# M220print.net
KiCad netlist of a schematic drawn in EAGLE
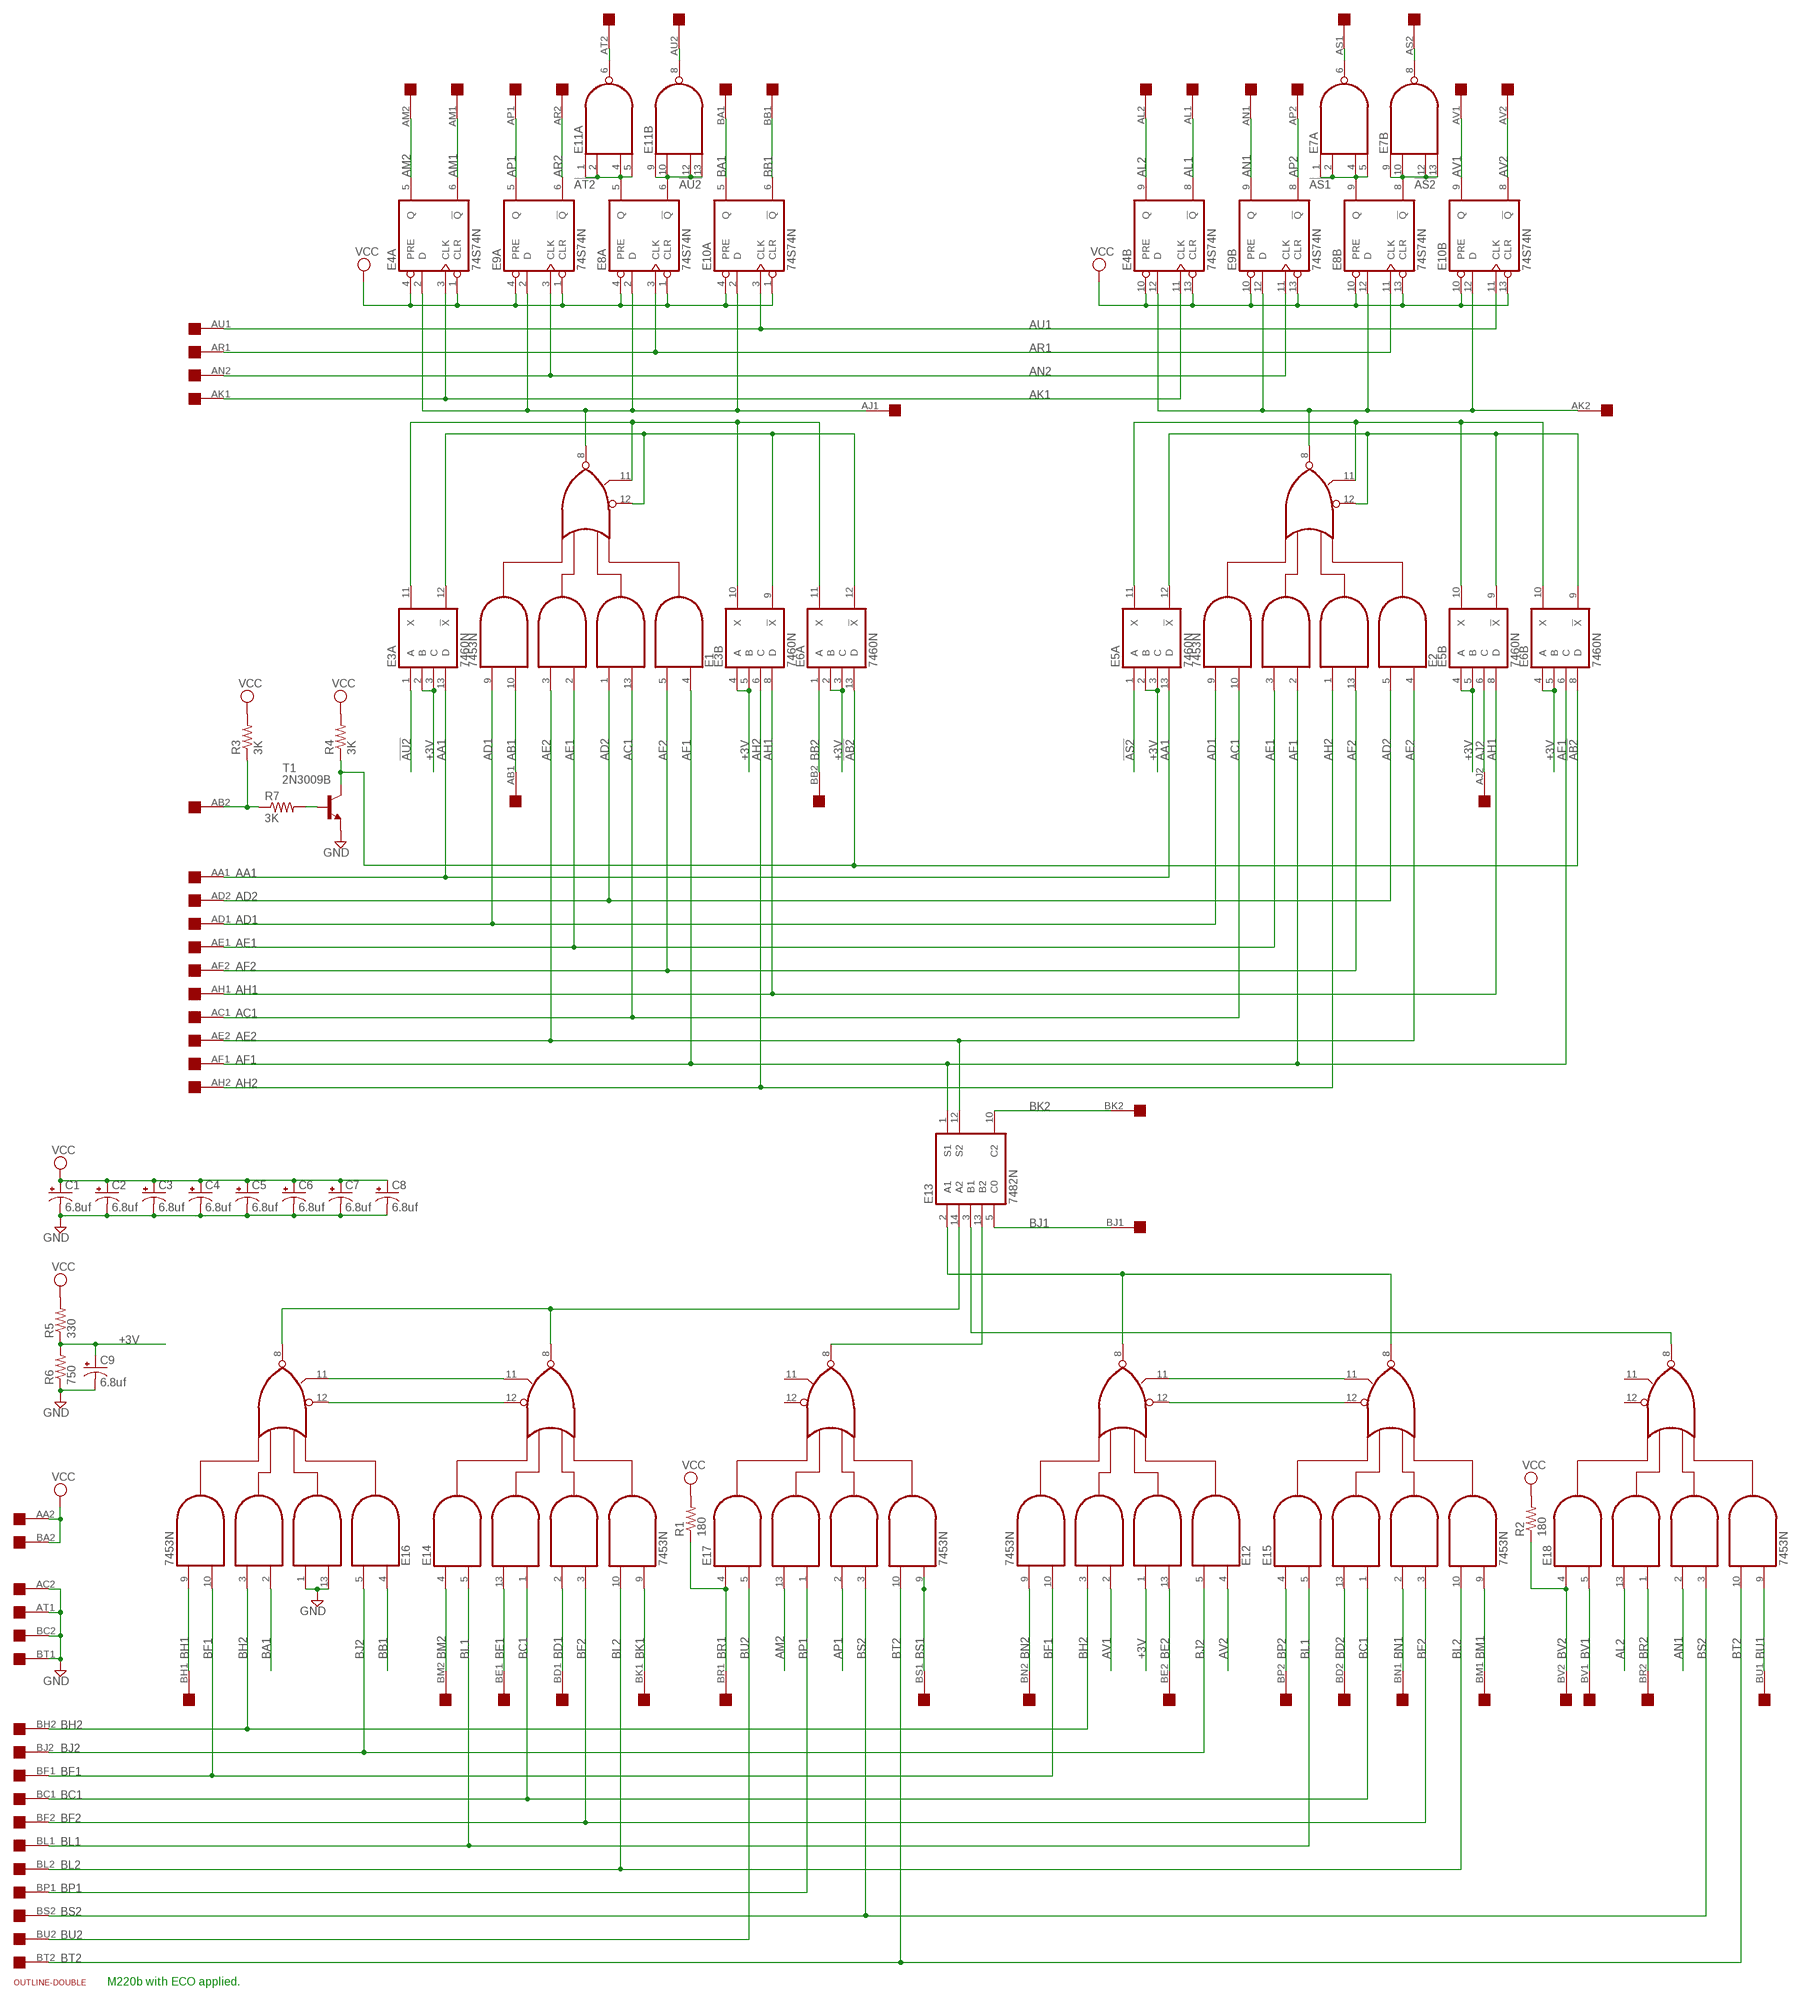
[diagram p0: schematic, sheet 1]

(export (version "E")
  (design (tool "Eeschema 10.0.6"))
  (components
    (comp (ref "C1")
      (value "6.8uf")
      (footprint "eagle-import:E15-5")
      (libsource (lib "eagle-import") (part "CPOL-USE15-5AXIAL"))
    )
    (comp (ref "C2")
      (value "6.8uf")
      (footprint "eagle-import:E15-5")
      (libsource (lib "eagle-import") (part "CPOL-USE15-5AXIAL"))
    )
    (comp (ref "C3")
      (value "6.8uf")
      (footprint "eagle-import:E15-5")
      (libsource (lib "eagle-import") (part "CPOL-USE15-5AXIAL"))
    )
    (comp (ref "C4")
      (value "6.8uf")
      (footprint "eagle-import:E15-5")
      (libsource (lib "eagle-import") (part "CPOL-USE15-5AXIAL"))
    )
    (comp (ref "C5")
      (value "6.8uf")
      (footprint "eagle-import:E15-5")
      (libsource (lib "eagle-import") (part "CPOL-USE15-5AXIAL"))
    )
    (comp (ref "C6")
      (value "6.8uf")
      (footprint "eagle-import:E15-5")
      (libsource (lib "eagle-import") (part "CPOL-USE15-5AXIAL"))
    )
    (comp (ref "C7")
      (value "6.8uf")
      (footprint "eagle-import:E15-5")
      (libsource (lib "eagle-import") (part "CPOL-USE15-5AXIAL"))
    )
    (comp (ref "C8")
      (value "6.8uf")
      (footprint "eagle-import:E15-5")
      (libsource (lib "eagle-import") (part "CPOL-USE15-5AXIAL"))
    )
    (comp (ref "C9")
      (value "6.8uf")
      (footprint "eagle-import:E15-5")
      (libsource (lib "eagle-import") (part "CPOL-USE15-5AXIAL"))
    )
    (comp (ref "E1")
      (value "7453N")
      (footprint "eagle-import:DIL14")
      (libsource (lib "eagle-import") (part "7453N"))
    )
    (comp (ref "E2")
      (value "7453N")
      (footprint "eagle-import:DIL14")
      (libsource (lib "eagle-import") (part "7453N"))
    )
    (comp (ref "E3")
      (value "7460N")
      (footprint "eagle-import:DIL14")
      (libsource (lib "eagle-import") (part "7460N"))
    )
    (comp (ref "E4")
      (value "74S74N")
      (footprint "eagle-import:DIL14")
      (libsource (lib "eagle-import") (part "7474NS"))
    )
    (comp (ref "E5")
      (value "7460N")
      (footprint "eagle-import:DIL14")
      (libsource (lib "eagle-import") (part "7460N"))
    )
    (comp (ref "E6")
      (value "7460N")
      (footprint "eagle-import:DIL14")
      (libsource (lib "eagle-import") (part "7460N"))
    )
    (comp (ref "E7")
      (value "74S20N")
      (footprint "eagle-import:DIL14")
      (libsource (lib "eagle-import") (part "7420NS"))
    )
    (comp (ref "E8")
      (value "74S74N")
      (footprint "eagle-import:DIL14")
      (libsource (lib "eagle-import") (part "7474NS"))
    )
    (comp (ref "E9")
      (value "74S74N")
      (footprint "eagle-import:DIL14")
      (libsource (lib "eagle-import") (part "7474NS"))
    )
    (comp (ref "E10")
      (value "74S74N")
      (footprint "eagle-import:DIL14")
      (libsource (lib "eagle-import") (part "7474NS"))
    )
    (comp (ref "E11")
      (value "74S20N")
      (footprint "eagle-import:DIL14")
      (libsource (lib "eagle-import") (part "7420NS"))
    )
    (comp (ref "E12")
      (value "7453N")
      (footprint "eagle-import:DIL14")
      (libsource (lib "eagle-import") (part "7453N"))
    )
    (comp (ref "E13")
      (value "7482N")
      (footprint "eagle-import:DIL14")
      (libsource (lib "eagle-import") (part "7482N"))
    )
    (comp (ref "E14")
      (value "7453N")
      (footprint "eagle-import:DIL14")
      (libsource (lib "eagle-import") (part "7453N"))
    )
    (comp (ref "E15")
      (value "7453N")
      (footprint "eagle-import:DIL14")
      (libsource (lib "eagle-import") (part "7453N"))
    )
    (comp (ref "E16")
      (value "7453N")
      (footprint "eagle-import:DIL14")
      (libsource (lib "eagle-import") (part "7453N"))
    )
    (comp (ref "E17")
      (value "7453N")
      (footprint "eagle-import:DIL14")
      (libsource (lib "eagle-import") (part "7453N"))
    )
    (comp (ref "E18")
      (value "7453N")
      (footprint "eagle-import:DIL14")
      (libsource (lib "eagle-import") (part "7453N"))
    )
    (comp (ref "R1")
      (value "180")
      (footprint "eagle-import:0207_10")
      (libsource (lib "eagle-import") (part "R-US_0207/10"))
    )
    (comp (ref "R2")
      (value "180")
      (footprint "eagle-import:0207_10")
      (libsource (lib "eagle-import") (part "R-US_0207/10"))
    )
    (comp (ref "R3")
      (value "3K")
      (footprint "eagle-import:0207_10")
      (libsource (lib "eagle-import") (part "R-US_0207/10"))
    )
    (comp (ref "R4")
      (value "3K")
      (footprint "eagle-import:0207_10")
      (libsource (lib "eagle-import") (part "R-US_0207/10"))
    )
    (comp (ref "R5")
      (value "330")
      (footprint "eagle-import:0207_10")
      (libsource (lib "eagle-import") (part "R-US_0207/10"))
    )
    (comp (ref "R6")
      (value "750")
      (footprint "eagle-import:0207_10")
      (libsource (lib "eagle-import") (part "R-US_0207/10"))
    )
    (comp (ref "R7")
      (value "3K")
      (footprint "eagle-import:0207_10")
      (libsource (lib "eagle-import") (part "R-US_0207/10"))
    )
    (comp (ref "T1")
      (value "2N3009B")
      (footprint "eagle-import:TO5")
      (libsource (lib "eagle-import") (part "2N1613"))
    )
    (comp (ref "U$1")
      (value "DOUBLE")
      (footprint "eagle-import:EDGE-CON4")
      (libsource (lib "eagle-import") (part "DOUBLE"))
    )
    (comp (ref "U$2")
      (value "OUTLINE-DOUBLE")
      (footprint "eagle-import:DOUBLE")
      (libsource (lib "eagle-import") (part "OUTLINE-DOUBLE"))
    )
  )
  (nets
    (net (code "1") (name "/+3V") (class "Default")
      (node (ref "C9") (pin "+") (pinfunction "+_+") (pintype "passive"))
      (node (ref "E12") (pin "1") (pinfunction "I4_1") (pintype "input"))
      (node (ref "E3") (pin "2") (pinfunction "B_2") (pintype "input"))
      (node (ref "E3") (pin "3") (pinfunction "C_3") (pintype "input"))
      (node (ref "E3") (pin "4") (pinfunction "A_4") (pintype "input"))
      (node (ref "E3") (pin "5") (pinfunction "B_5") (pintype "input"))
      (node (ref "E5") (pin "2") (pinfunction "B_2") (pintype "input"))
      (node (ref "E5") (pin "3") (pinfunction "C_3") (pintype "input"))
      (node (ref "E5") (pin "4") (pinfunction "A_4") (pintype "input"))
      (node (ref "E5") (pin "5") (pinfunction "B_5") (pintype "input"))
      (node (ref "E6") (pin "2") (pinfunction "B_2") (pintype "input"))
      (node (ref "E6") (pin "3") (pinfunction "C_3") (pintype "input"))
      (node (ref "E6") (pin "4") (pinfunction "A_4") (pintype "input"))
      (node (ref "E6") (pin "5") (pinfunction "B_5") (pintype "input"))
      (node (ref "R5") (pin "1") (pinfunction "1_1") (pintype "passive"))
      (node (ref "R6") (pin "2") (pinfunction "2_2") (pintype "passive"))
    )
    (net (code "2") (name "/AA1") (class "Default")
      (node (ref "E3") (pin "13") (pinfunction "D_13") (pintype "input"))
      (node (ref "E5") (pin "13") (pinfunction "D_13") (pintype "input"))
      (node (ref "U$1") (pin "AA1") (pinfunction "1_AA1") (pintype "passive"))
    )
    (net (code "3") (name "/AB1") (class "Default")
      (node (ref "E1") (pin "10") (pinfunction "I7_10") (pintype "input"))
      (node (ref "U$1") (pin "AB1") (pinfunction "1_AB1") (pintype "passive"))
    )
    (net (code "4") (name "/AC1") (class "Default")
      (node (ref "E1") (pin "13") (pinfunction "I3_13") (pintype "input"))
      (node (ref "E2") (pin "10") (pinfunction "I7_10") (pintype "input"))
      (node (ref "U$1") (pin "AC1") (pinfunction "1_AC1") (pintype "passive"))
    )
    (net (code "5") (name "/AD1") (class "Default")
      (node (ref "E1") (pin "9") (pinfunction "I8_9") (pintype "input"))
      (node (ref "E2") (pin "9") (pinfunction "I8_9") (pintype "input"))
      (node (ref "U$1") (pin "AD1") (pinfunction "1_AD1") (pintype "passive"))
    )
    (net (code "6") (name "/AD2") (class "Default")
      (node (ref "E1") (pin "1") (pinfunction "I4_1") (pintype "input"))
      (node (ref "E2") (pin "5") (pinfunction "I2_5") (pintype "input"))
      (node (ref "U$1") (pin "AD2") (pinfunction "1_AD2") (pintype "passive"))
    )
    (net (code "7") (name "/AE1") (class "Default")
      (node (ref "E1") (pin "2") (pinfunction "I5_2") (pintype "input"))
      (node (ref "E2") (pin "3") (pinfunction "I6_3") (pintype "input"))
      (node (ref "U$1") (pin "AE1") (pinfunction "1_AE1") (pintype "passive"))
    )
    (net (code "8") (name "/AE2") (class "Default")
      (node (ref "E1") (pin "3") (pinfunction "I6_3") (pintype "input"))
      (node (ref "E13") (pin "12") (pinfunction "S2_12") (pintype "output"))
      (node (ref "E2") (pin "4") (pinfunction "I1_4") (pintype "input"))
      (node (ref "U$1") (pin "AE2") (pinfunction "1_AE2") (pintype "passive"))
    )
    (net (code "9") (name "/AF1") (class "Default")
      (node (ref "E1") (pin "4") (pinfunction "I1_4") (pintype "input"))
      (node (ref "E13") (pin "1") (pinfunction "S1_1") (pintype "output"))
      (node (ref "E2") (pin "2") (pinfunction "I5_2") (pintype "input"))
      (node (ref "E6") (pin "6") (pinfunction "C_6") (pintype "input"))
      (node (ref "U$1") (pin "AF1") (pinfunction "1_AF1") (pintype "passive"))
    )
    (net (code "10") (name "/AF2") (class "Default")
      (node (ref "E1") (pin "5") (pinfunction "I2_5") (pintype "input"))
      (node (ref "E2") (pin "13") (pinfunction "I3_13") (pintype "input"))
      (node (ref "U$1") (pin "AF2") (pinfunction "1_AF2") (pintype "passive"))
    )
    (net (code "11") (name "/AH1") (class "Default")
      (node (ref "E3") (pin "8") (pinfunction "D_8") (pintype "input"))
      (node (ref "E5") (pin "8") (pinfunction "D_8") (pintype "input"))
      (node (ref "U$1") (pin "AH1") (pinfunction "1_AH1") (pintype "passive"))
    )
    (net (code "12") (name "/AH2") (class "Default")
      (node (ref "E2") (pin "1") (pinfunction "I4_1") (pintype "input"))
      (node (ref "E3") (pin "6") (pinfunction "C_6") (pintype "input"))
      (node (ref "U$1") (pin "AH2") (pinfunction "1_AH2") (pintype "passive"))
    )
    (net (code "13") (name "/AJ2") (class "Default")
      (node (ref "E5") (pin "6") (pinfunction "C_6") (pintype "input"))
      (node (ref "U$1") (pin "AJ2") (pinfunction "1_AJ2") (pintype "passive"))
    )
    (net (code "14") (name "/AK1") (class "Default")
      (node (ref "E4") (pin "11") (pinfunction "CLK_11") (pintype "input"))
      (node (ref "E4") (pin "3") (pinfunction "CLK_3") (pintype "input"))
      (node (ref "U$1") (pin "AK1") (pinfunction "1_AK1") (pintype "passive"))
    )
    (net (code "15") (name "/AL1") (class "Default")
      (node (ref "E4") (pin "8") (pinfunction "~{Q}_8") (pintype "output"))
      (node (ref "U$1") (pin "AL1") (pinfunction "1_AL1") (pintype "passive"))
    )
    (net (code "16") (name "/AL2") (class "Default")
      (node (ref "E18") (pin "13") (pinfunction "I3_13") (pintype "input"))
      (node (ref "E4") (pin "9") (pinfunction "Q_9") (pintype "output"))
      (node (ref "U$1") (pin "AL2") (pinfunction "1_AL2") (pintype "passive"))
    )
    (net (code "17") (name "/AM1") (class "Default")
      (node (ref "E4") (pin "6") (pinfunction "~{Q}_6") (pintype "output"))
      (node (ref "U$1") (pin "AM1") (pinfunction "1_AM1") (pintype "passive"))
    )
    (net (code "18") (name "/AM2") (class "Default")
      (node (ref "E17") (pin "13") (pinfunction "I3_13") (pintype "input"))
      (node (ref "E4") (pin "5") (pinfunction "Q_5") (pintype "output"))
      (node (ref "U$1") (pin "AM2") (pinfunction "1_AM2") (pintype "passive"))
    )
    (net (code "19") (name "/AN1") (class "Default")
      (node (ref "E18") (pin "2") (pinfunction "I5_2") (pintype "input"))
      (node (ref "E9") (pin "9") (pinfunction "Q_9") (pintype "output"))
      (node (ref "U$1") (pin "AN1") (pinfunction "1_AN1") (pintype "passive"))
    )
    (net (code "20") (name "/AN2") (class "Default")
      (node (ref "E9") (pin "11") (pinfunction "CLK_11") (pintype "input"))
      (node (ref "E9") (pin "3") (pinfunction "CLK_3") (pintype "input"))
      (node (ref "U$1") (pin "AN2") (pinfunction "1_AN2") (pintype "passive"))
    )
    (net (code "21") (name "/AP1") (class "Default")
      (node (ref "E17") (pin "2") (pinfunction "I5_2") (pintype "input"))
      (node (ref "E9") (pin "5") (pinfunction "Q_5") (pintype "output"))
      (node (ref "U$1") (pin "AP1") (pinfunction "1_AP1") (pintype "passive"))
    )
    (net (code "22") (name "/AP2") (class "Default")
      (node (ref "E9") (pin "8") (pinfunction "~{Q}_8") (pintype "output"))
      (node (ref "U$1") (pin "AP2") (pinfunction "1_AP2") (pintype "passive"))
    )
    (net (code "23") (name "/AR1") (class "Default")
      (node (ref "E8") (pin "11") (pinfunction "CLK_11") (pintype "input"))
      (node (ref "E8") (pin "3") (pinfunction "CLK_3") (pintype "input"))
      (node (ref "U$1") (pin "AR1") (pinfunction "1_AR1") (pintype "passive"))
    )
    (net (code "24") (name "/AR2") (class "Default")
      (node (ref "E9") (pin "6") (pinfunction "~{Q}_6") (pintype "output"))
      (node (ref "U$1") (pin "AR2") (pinfunction "1_AR2") (pintype "passive"))
    )
    (net (code "25") (name "/AU1") (class "Default")
      (node (ref "E10") (pin "11") (pinfunction "CLK_11") (pintype "input"))
      (node (ref "E10") (pin "3") (pinfunction "CLK_3") (pintype "input"))
      (node (ref "U$1") (pin "AU1") (pinfunction "1_AU1") (pintype "passive"))
    )
    (net (code "26") (name "/AV1") (class "Default")
      (node (ref "E10") (pin "9") (pinfunction "Q_9") (pintype "output"))
      (node (ref "E12") (pin "2") (pinfunction "I5_2") (pintype "input"))
      (node (ref "U$1") (pin "AV1") (pinfunction "1_AV1") (pintype "passive"))
    )
    (net (code "27") (name "/AV2") (class "Default")
      (node (ref "E10") (pin "8") (pinfunction "~{Q}_8") (pintype "output"))
      (node (ref "E12") (pin "4") (pinfunction "I1_4") (pintype "input"))
      (node (ref "U$1") (pin "AV2") (pinfunction "1_AV2") (pintype "passive"))
    )
    (net (code "28") (name "/BA1") (class "Default")
      (node (ref "E10") (pin "5") (pinfunction "Q_5") (pintype "output"))
      (node (ref "E16") (pin "2") (pinfunction "I5_2") (pintype "input"))
      (node (ref "U$1") (pin "BA1") (pinfunction "1_BA1") (pintype "passive"))
    )
    (net (code "29") (name "/BB1") (class "Default")
      (node (ref "E10") (pin "6") (pinfunction "~{Q}_6") (pintype "output"))
      (node (ref "E16") (pin "4") (pinfunction "I1_4") (pintype "input"))
      (node (ref "U$1") (pin "BB1") (pinfunction "1_BB1") (pintype "passive"))
    )
    (net (code "30") (name "/BB2") (class "Default")
      (node (ref "E6") (pin "1") (pinfunction "A_1") (pintype "input"))
      (node (ref "U$1") (pin "BB2") (pinfunction "1_BB2") (pintype "passive"))
    )
    (net (code "31") (name "/BC1") (class "Default")
      (node (ref "E14") (pin "1") (pinfunction "I4_1") (pintype "input"))
      (node (ref "E15") (pin "1") (pinfunction "I4_1") (pintype "input"))
      (node (ref "U$1") (pin "BC1") (pinfunction "1_BC1") (pintype "passive"))
    )
    (net (code "32") (name "/BD1") (class "Default")
      (node (ref "E14") (pin "2") (pinfunction "I5_2") (pintype "input"))
      (node (ref "U$1") (pin "BD1") (pinfunction "1_BD1") (pintype "passive"))
    )
    (net (code "33") (name "/BD2") (class "Default")
      (node (ref "E15") (pin "13") (pinfunction "I3_13") (pintype "input"))
      (node (ref "U$1") (pin "BD2") (pinfunction "1_BD2") (pintype "passive"))
    )
    (net (code "34") (name "/BE1") (class "Default")
      (node (ref "E14") (pin "13") (pinfunction "I3_13") (pintype "input"))
      (node (ref "U$1") (pin "BE1") (pinfunction "1_BE1") (pintype "passive"))
    )
    (net (code "35") (name "/BE2") (class "Default")
      (node (ref "E12") (pin "13") (pinfunction "I3_13") (pintype "input"))
      (node (ref "U$1") (pin "BE2") (pinfunction "1_BE2") (pintype "passive"))
    )
    (net (code "36") (name "/BF1") (class "Default")
      (node (ref "E12") (pin "10") (pinfunction "I7_10") (pintype "input"))
      (node (ref "E16") (pin "10") (pinfunction "I7_10") (pintype "input"))
      (node (ref "U$1") (pin "BF1") (pinfunction "1_BF1") (pintype "passive"))
    )
    (net (code "37") (name "/BF2") (class "Default")
      (node (ref "E14") (pin "3") (pinfunction "I6_3") (pintype "input"))
      (node (ref "E15") (pin "3") (pinfunction "I6_3") (pintype "input"))
      (node (ref "U$1") (pin "BF2") (pinfunction "1_BF2") (pintype "passive"))
    )
    (net (code "38") (name "/BH1") (class "Default")
      (node (ref "E16") (pin "9") (pinfunction "I8_9") (pintype "input"))
      (node (ref "U$1") (pin "BH1") (pinfunction "1_BH1") (pintype "passive"))
    )
    (net (code "39") (name "/BH2") (class "Default")
      (node (ref "E12") (pin "3") (pinfunction "I6_3") (pintype "input"))
      (node (ref "E16") (pin "3") (pinfunction "I6_3") (pintype "input"))
      (node (ref "U$1") (pin "BH2") (pinfunction "1_BH2") (pintype "passive"))
    )
    (net (code "40") (name "/BJ1") (class "Default")
      (node (ref "E13") (pin "5") (pinfunction "C0_5") (pintype "input"))
      (node (ref "U$1") (pin "BJ1") (pinfunction "1_BJ1") (pintype "passive"))
    )
    (net (code "41") (name "/BJ2") (class "Default")
      (node (ref "E12") (pin "5") (pinfunction "I2_5") (pintype "input"))
      (node (ref "E16") (pin "5") (pinfunction "I2_5") (pintype "input"))
      (node (ref "U$1") (pin "BJ2") (pinfunction "1_BJ2") (pintype "passive"))
    )
    (net (code "42") (name "/BK1") (class "Default")
      (node (ref "E14") (pin "9") (pinfunction "I8_9") (pintype "input"))
      (node (ref "U$1") (pin "BK1") (pinfunction "1_BK1") (pintype "passive"))
    )
    (net (code "43") (name "/BK2") (class "Default")
      (node (ref "E13") (pin "10") (pinfunction "C2_10") (pintype "output"))
      (node (ref "U$1") (pin "BK2") (pinfunction "1_BK2") (pintype "passive"))
    )
    (net (code "44") (name "/BL1") (class "Default")
      (node (ref "E14") (pin "5") (pinfunction "I2_5") (pintype "input"))
      (node (ref "E15") (pin "5") (pinfunction "I2_5") (pintype "input"))
      (node (ref "U$1") (pin "BL1") (pinfunction "1_BL1") (pintype "passive"))
    )
    (net (code "45") (name "/BL2") (class "Default")
      (node (ref "E14") (pin "10") (pinfunction "I7_10") (pintype "input"))
      (node (ref "E15") (pin "10") (pinfunction "I7_10") (pintype "input"))
      (node (ref "U$1") (pin "BL2") (pinfunction "1_BL2") (pintype "passive"))
    )
    (net (code "46") (name "/BM1") (class "Default")
      (node (ref "E15") (pin "9") (pinfunction "I8_9") (pintype "input"))
      (node (ref "U$1") (pin "BM1") (pinfunction "1_BM1") (pintype "passive"))
    )
    (net (code "47") (name "/BM2") (class "Default")
      (node (ref "E14") (pin "4") (pinfunction "I1_4") (pintype "input"))
      (node (ref "U$1") (pin "BM2") (pinfunction "1_BM2") (pintype "passive"))
    )
    (net (code "48") (name "/BN1") (class "Default")
      (node (ref "E15") (pin "2") (pinfunction "I5_2") (pintype "input"))
      (node (ref "U$1") (pin "BN1") (pinfunction "1_BN1") (pintype "passive"))
    )
    (net (code "49") (name "/BN2") (class "Default")
      (node (ref "E12") (pin "9") (pinfunction "I8_9") (pintype "input"))
      (node (ref "U$1") (pin "BN2") (pinfunction "1_BN2") (pintype "passive"))
    )
    (net (code "50") (name "/BP1") (class "Default")
      (node (ref "E17") (pin "1") (pinfunction "I4_1") (pintype "input"))
      (node (ref "U$1") (pin "BP1") (pinfunction "1_BP1") (pintype "passive"))
    )
    (net (code "51") (name "/BP2") (class "Default")
      (node (ref "E15") (pin "4") (pinfunction "I1_4") (pintype "input"))
      (node (ref "U$1") (pin "BP2") (pinfunction "1_BP2") (pintype "passive"))
    )
    (net (code "52") (name "/BR1") (class "Default")
      (node (ref "E17") (pin "4") (pinfunction "I1_4") (pintype "input"))
      (node (ref "R1") (pin "1") (pinfunction "1_1") (pintype "passive"))
      (node (ref "U$1") (pin "BR1") (pinfunction "1_BR1") (pintype "passive"))
    )
    (net (code "53") (name "/BR2") (class "Default")
      (node (ref "E18") (pin "1") (pinfunction "I4_1") (pintype "input"))
      (node (ref "U$1") (pin "BR2") (pinfunction "1_BR2") (pintype "passive"))
    )
    (net (code "54") (name "/BS1") (class "Default")
      (node (ref "E17") (pin "9") (pinfunction "I8_9") (pintype "input"))
      (node (ref "U$1") (pin "BS1") (pinfunction "1_BS1") (pintype "passive"))
    )
    (net (code "55") (name "/BS2") (class "Default")
      (node (ref "E17") (pin "3") (pinfunction "I6_3") (pintype "input"))
      (node (ref "E18") (pin "3") (pinfunction "I6_3") (pintype "input"))
      (node (ref "U$1") (pin "BS2") (pinfunction "1_BS2") (pintype "passive"))
    )
    (net (code "56") (name "/BT2") (class "Default")
      (node (ref "E17") (pin "10") (pinfunction "I7_10") (pintype "input"))
      (node (ref "E18") (pin "10") (pinfunction "I7_10") (pintype "input"))
      (node (ref "U$1") (pin "BT2") (pinfunction "1_BT2") (pintype "passive"))
    )
    (net (code "57") (name "/BU1") (class "Default")
      (node (ref "E18") (pin "9") (pinfunction "I8_9") (pintype "input"))
      (node (ref "U$1") (pin "BU1") (pinfunction "1_BU1") (pintype "passive"))
    )
    (net (code "58") (name "/BU2") (class "Default")
      (node (ref "E17") (pin "5") (pinfunction "I2_5") (pintype "input"))
      (node (ref "U$1") (pin "BU2") (pinfunction "1_BU2") (pintype "passive"))
    )
    (net (code "59") (name "/BV1") (class "Default")
      (node (ref "E18") (pin "5") (pinfunction "I2_5") (pintype "input"))
      (node (ref "U$1") (pin "BV1") (pinfunction "1_BV1") (pintype "passive"))
    )
    (net (code "60") (name "/BV2") (class "Default")
      (node (ref "E18") (pin "4") (pinfunction "I1_4") (pintype "input"))
      (node (ref "R2") (pin "1") (pinfunction "1_1") (pintype "passive"))
      (node (ref "U$1") (pin "BV2") (pinfunction "1_BV2") (pintype "passive"))
    )
    (net (code "61") (name "/~{AB2}") (class "Default")
      (node (ref "E6") (pin "13") (pinfunction "D_13") (pintype "input"))
      (node (ref "E6") (pin "8") (pinfunction "D_8") (pintype "input"))
      (node (ref "R4") (pin "1") (pinfunction "1_1") (pintype "passive"))
      (node (ref "T1") (pin "3") (pinfunction "C_3") (pintype "passive"))
    )
    (net (code "62") (name "/~{AS1}") (class "Default")
      (node (ref "E7") (pin "1") (pinfunction "I0_1") (pintype "input"))
      (node (ref "E7") (pin "2") (pinfunction "I1_2") (pintype "input"))
      (node (ref "E7") (pin "4") (pinfunction "I2_4") (pintype "input"))
      (node (ref "E7") (pin "5") (pinfunction "I3_5") (pintype "input"))
      (node (ref "E8") (pin "9") (pinfunction "Q_9") (pintype "output"))
    )
    (net (code "63") (name "/~{AS2}") (class "Default")
      (node (ref "E5") (pin "1") (pinfunction "A_1") (pintype "input"))
      (node (ref "E7") (pin "10") (pinfunction "I1_10") (pintype "input"))
      (node (ref "E7") (pin "12") (pinfunction "I2_12") (pintype "input"))
      (node (ref "E7") (pin "13") (pinfunction "I3_13") (pintype "input"))
      (node (ref "E7") (pin "9") (pinfunction "I0_9") (pintype "input"))
      (node (ref "E8") (pin "8") (pinfunction "~{Q}_8") (pintype "output"))
    )
    (net (code "64") (name "/~{AT2}") (class "Default")
      (node (ref "E11") (pin "1") (pinfunction "I0_1") (pintype "input"))
      (node (ref "E11") (pin "2") (pinfunction "I1_2") (pintype "input"))
      (node (ref "E11") (pin "4") (pinfunction "I2_4") (pintype "input"))
      (node (ref "E11") (pin "5") (pinfunction "I3_5") (pintype "input"))
      (node (ref "E8") (pin "5") (pinfunction "Q_5") (pintype "output"))
    )
    (net (code "65") (name "/~{AU2}") (class "Default")
      (node (ref "E11") (pin "10") (pinfunction "I1_10") (pintype "input"))
      (node (ref "E11") (pin "12") (pinfunction "I2_12") (pintype "input"))
      (node (ref "E11") (pin "13") (pinfunction "I3_13") (pintype "input"))
      (node (ref "E11") (pin "9") (pinfunction "I0_9") (pintype "input"))
      (node (ref "E3") (pin "1") (pinfunction "A_1") (pintype "input"))
      (node (ref "E8") (pin "6") (pinfunction "~{Q}_6") (pintype "output"))
    )
    (net (code "66") (name "GND") (class "Default")
      (node (ref "C1") (pin "-") (pinfunction "-_-") (pintype "passive"))
      (node (ref "C2") (pin "-") (pinfunction "-_-") (pintype "passive"))
      (node (ref "C3") (pin "-") (pinfunction "-_-") (pintype "passive"))
      (node (ref "C4") (pin "-") (pinfunction "-_-") (pintype "passive"))
      (node (ref "C5") (pin "-") (pinfunction "-_-") (pintype "passive"))
      (node (ref "C6") (pin "-") (pinfunction "-_-") (pintype "passive"))
      (node (ref "C7") (pin "-") (pinfunction "-_-") (pintype "passive"))
      (node (ref "C8") (pin "-") (pinfunction "-_-") (pintype "passive"))
      (node (ref "C9") (pin "-") (pinfunction "-_-") (pintype "passive"))
      (node (ref "E16") (pin "1") (pinfunction "I4_1") (pintype "input"))
      (node (ref "E16") (pin "13") (pinfunction "I3_13") (pintype "input"))
      (node (ref "R6") (pin "1") (pinfunction "1_1") (pintype "passive"))
      (node (ref "T1") (pin "1") (pinfunction "E_1") (pintype "passive"))
      (node (ref "U$1") (pin "AC2") (pinfunction "1_AC2") (pintype "passive"))
      (node (ref "U$1") (pin "AT1") (pinfunction "1_AT1") (pintype "passive"))
      (node (ref "U$1") (pin "BC2") (pinfunction "1_BC2") (pintype "passive"))
      (node (ref "U$1") (pin "BT1") (pinfunction "1_BT1") (pintype "passive"))
    )
    (net (code "67") (name "Net-(E1A-I9)") (class "Default")
      (node (ref "E1") (pin "12") (pinfunction "I9_12") (pintype "passive"))
      (node (ref "E3") (pin "12") (pinfunction "~{X}_12") (pintype "output"))
      (node (ref "E3") (pin "9") (pinfunction "~{X}_9") (pintype "output"))
      (node (ref "E6") (pin "12") (pinfunction "~{X}_12") (pintype "output"))
    )
    (net (code "68") (name "Net-(E1A-I10)") (class "Default")
      (node (ref "E1") (pin "11") (pinfunction "I10_11") (pintype "passive"))
      (node (ref "E3") (pin "10") (pinfunction "X_10") (pintype "output"))
      (node (ref "E3") (pin "11") (pinfunction "X_11") (pintype "output"))
      (node (ref "E6") (pin "11") (pinfunction "X_11") (pintype "output"))
    )
    (net (code "69") (name "Net-(E2A-I9)") (class "Default")
      (node (ref "E2") (pin "12") (pinfunction "I9_12") (pintype "passive"))
      (node (ref "E5") (pin "12") (pinfunction "~{X}_12") (pintype "output"))
      (node (ref "E5") (pin "9") (pinfunction "~{X}_9") (pintype "output"))
      (node (ref "E6") (pin "9") (pinfunction "~{X}_9") (pintype "output"))
    )
    (net (code "70") (name "Net-(E2A-I10)") (class "Default")
      (node (ref "E2") (pin "11") (pinfunction "I10_11") (pintype "passive"))
      (node (ref "E5") (pin "10") (pinfunction "X_10") (pintype "output"))
      (node (ref "E5") (pin "11") (pinfunction "X_11") (pintype "output"))
      (node (ref "E6") (pin "10") (pinfunction "X_10") (pintype "output"))
    )
    (net (code "71") (name "Net-(E7A-O)") (class "Default")
      (node (ref "E7") (pin "6") (pinfunction "O_6") (pintype "output"))
      (node (ref "U$1") (pin "AS1") (pinfunction "1_AS1") (pintype "passive"))
    )
    (net (code "72") (name "Net-(E7B-O)") (class "Default")
      (node (ref "E7") (pin "8") (pinfunction "O_8") (pintype "output"))
      (node (ref "U$1") (pin "AS2") (pinfunction "1_AS2") (pintype "passive"))
    )
    (net (code "73") (name "Net-(E10A-D)") (class "Default")
      (node (ref "E1") (pin "8") (pinfunction "O_8") (pintype "output"))
      (node (ref "E10") (pin "2") (pinfunction "D_2") (pintype "input"))
      (node (ref "E4") (pin "2") (pinfunction "D_2") (pintype "input"))
      (node (ref "E8") (pin "2") (pinfunction "D_2") (pintype "input"))
      (node (ref "E9") (pin "2") (pinfunction "D_2") (pintype "input"))
      (node (ref "U$1") (pin "AJ1") (pinfunction "1_AJ1") (pintype "passive"))
    )
    (net (code "74") (name "Net-(E10B-D)") (class "Default")
      (node (ref "E10") (pin "12") (pinfunction "D_12") (pintype "input"))
      (node (ref "E2") (pin "8") (pinfunction "O_8") (pintype "output"))
      (node (ref "E4") (pin "12") (pinfunction "D_12") (pintype "input"))
      (node (ref "E8") (pin "12") (pinfunction "D_12") (pintype "input"))
      (node (ref "E9") (pin "12") (pinfunction "D_12") (pintype "input"))
      (node (ref "U$1") (pin "AK2") (pinfunction "1_AK2") (pintype "passive"))
    )
    (net (code "75") (name "Net-(E11A-O)") (class "Default")
      (node (ref "E11") (pin "6") (pinfunction "O_6") (pintype "output"))
      (node (ref "U$1") (pin "AT2") (pinfunction "1_AT2") (pintype "passive"))
    )
    (net (code "76") (name "Net-(E11B-O)") (class "Default")
      (node (ref "E11") (pin "8") (pinfunction "O_8") (pintype "output"))
      (node (ref "U$1") (pin "AU2") (pinfunction "1_AU2") (pintype "passive"))
    )
    (net (code "77") (name "Net-(E12A-I9)") (class "Default")
      (node (ref "E12") (pin "12") (pinfunction "I9_12") (pintype "passive"))
      (node (ref "E15") (pin "12") (pinfunction "I9_12") (pintype "passive"))
    )
    (net (code "78") (name "Net-(E12A-I10)") (class "Default")
      (node (ref "E12") (pin "11") (pinfunction "I10_11") (pintype "passive"))
      (node (ref "E15") (pin "11") (pinfunction "I10_11") (pintype "passive"))
    )
    (net (code "79") (name "Net-(E12A-O)") (class "Default")
      (node (ref "E12") (pin "8") (pinfunction "O_8") (pintype "output"))
      (node (ref "E13") (pin "2") (pinfunction "A1_2") (pintype "input"))
      (node (ref "E15") (pin "8") (pinfunction "O_8") (pintype "output"))
    )
    (net (code "80") (name "Net-(E13A-A2)") (class "Default")
      (node (ref "E13") (pin "14") (pinfunction "A2_14") (pintype "input"))
      (node (ref "E14") (pin "8") (pinfunction "O_8") (pintype "output"))
      (node (ref "E16") (pin "8") (pinfunction "O_8") (pintype "output"))
    )
    (net (code "81") (name "Net-(E13A-B1)") (class "Default")
      (node (ref "E13") (pin "3") (pinfunction "B1_3") (pintype "input"))
      (node (ref "E18") (pin "8") (pinfunction "O_8") (pintype "output"))
    )
    (net (code "82") (name "Net-(E13A-B2)") (class "Default")
      (node (ref "E13") (pin "13") (pinfunction "B2_13") (pintype "input"))
      (node (ref "E17") (pin "8") (pinfunction "O_8") (pintype "output"))
    )
    (net (code "83") (name "Net-(E14A-I9)") (class "Default")
      (node (ref "E14") (pin "12") (pinfunction "I9_12") (pintype "passive"))
      (node (ref "E16") (pin "12") (pinfunction "I9_12") (pintype "passive"))
    )
    (net (code "84") (name "Net-(E14A-I10)") (class "Default")
      (node (ref "E14") (pin "11") (pinfunction "I10_11") (pintype "passive"))
      (node (ref "E16") (pin "11") (pinfunction "I10_11") (pintype "passive"))
    )
    (net (code "85") (name "Net-(T1-B)") (class "Default")
      (node (ref "R7") (pin "2") (pinfunction "2_2") (pintype "passive"))
      (node (ref "T1") (pin "2") (pinfunction "B_2") (pintype "passive"))
    )
    (net (code "86") (name "Net-(U$1D-1)") (class "Default")
      (node (ref "R3") (pin "1") (pinfunction "1_1") (pintype "passive"))
      (node (ref "R7") (pin "1") (pinfunction "1_1") (pintype "passive"))
      (node (ref "U$1") (pin "AB2") (pinfunction "1_AB2") (pintype "passive"))
    )
    (net (code "87") (name "VCC") (class "Default")
      (node (ref "C1") (pin "+") (pinfunction "+_+") (pintype "passive"))
      (node (ref "C2") (pin "+") (pinfunction "+_+") (pintype "passive"))
      (node (ref "C3") (pin "+") (pinfunction "+_+") (pintype "passive"))
      (node (ref "C4") (pin "+") (pinfunction "+_+") (pintype "passive"))
      (node (ref "C5") (pin "+") (pinfunction "+_+") (pintype "passive"))
      (node (ref "C6") (pin "+") (pinfunction "+_+") (pintype "passive"))
      (node (ref "C7") (pin "+") (pinfunction "+_+") (pintype "passive"))
      (node (ref "C8") (pin "+") (pinfunction "+_+") (pintype "passive"))
      (node (ref "E10") (pin "1") (pinfunction "CLR_1") (pintype "input"))
      (node (ref "E10") (pin "10") (pinfunction "PRE_10") (pintype "input"))
      (node (ref "E10") (pin "13") (pinfunction "CLR_13") (pintype "input"))
      (node (ref "E10") (pin "4") (pinfunction "PRE_4") (pintype "input"))
      (node (ref "E4") (pin "1") (pinfunction "CLR_1") (pintype "input"))
      (node (ref "E4") (pin "10") (pinfunction "PRE_10") (pintype "input"))
      (node (ref "E4") (pin "13") (pinfunction "CLR_13") (pintype "input"))
      (node (ref "E4") (pin "4") (pinfunction "PRE_4") (pintype "input"))
      (node (ref "E8") (pin "1") (pinfunction "CLR_1") (pintype "input"))
      (node (ref "E8") (pin "10") (pinfunction "PRE_10") (pintype "input"))
      (node (ref "E8") (pin "13") (pinfunction "CLR_13") (pintype "input"))
      (node (ref "E8") (pin "4") (pinfunction "PRE_4") (pintype "input"))
      (node (ref "E9") (pin "1") (pinfunction "CLR_1") (pintype "input"))
      (node (ref "E9") (pin "10") (pinfunction "PRE_10") (pintype "input"))
      (node (ref "E9") (pin "13") (pinfunction "CLR_13") (pintype "input"))
      (node (ref "E9") (pin "4") (pinfunction "PRE_4") (pintype "input"))
      (node (ref "R1") (pin "2") (pinfunction "2_2") (pintype "passive"))
      (node (ref "R2") (pin "2") (pinfunction "2_2") (pintype "passive"))
      (node (ref "R3") (pin "2") (pinfunction "2_2") (pintype "passive"))
      (node (ref "R4") (pin "2") (pinfunction "2_2") (pintype "passive"))
      (node (ref "R5") (pin "2") (pinfunction "2_2") (pintype "passive"))
      (node (ref "U$1") (pin "AA2") (pinfunction "1_AA2") (pintype "passive"))
      (node (ref "U$1") (pin "BA2") (pinfunction "1_BA2") (pintype "passive"))
    )
    (net (code "88") (name "unconnected-(E17A-I9-Pad12)") (class "Default")
      (node (ref "E17") (pin "12") (pinfunction "I9_12") (pintype "passive"))
    )
    (net (code "89") (name "unconnected-(E17A-I10-Pad11)") (class "Default")
      (node (ref "E17") (pin "11") (pinfunction "I10_11") (pintype "passive"))
    )
    (net (code "90") (name "unconnected-(E18A-I9-Pad12)") (class "Default")
      (node (ref "E18") (pin "12") (pinfunction "I9_12") (pintype "passive"))
    )
    (net (code "91") (name "unconnected-(E18A-I10-Pad11)") (class "Default")
      (node (ref "E18") (pin "11") (pinfunction "I10_11") (pintype "passive"))
    )
  )
)
